# 8266_NFC_reader.net
KiCad netlist of a schematic drawn in EasyEDA
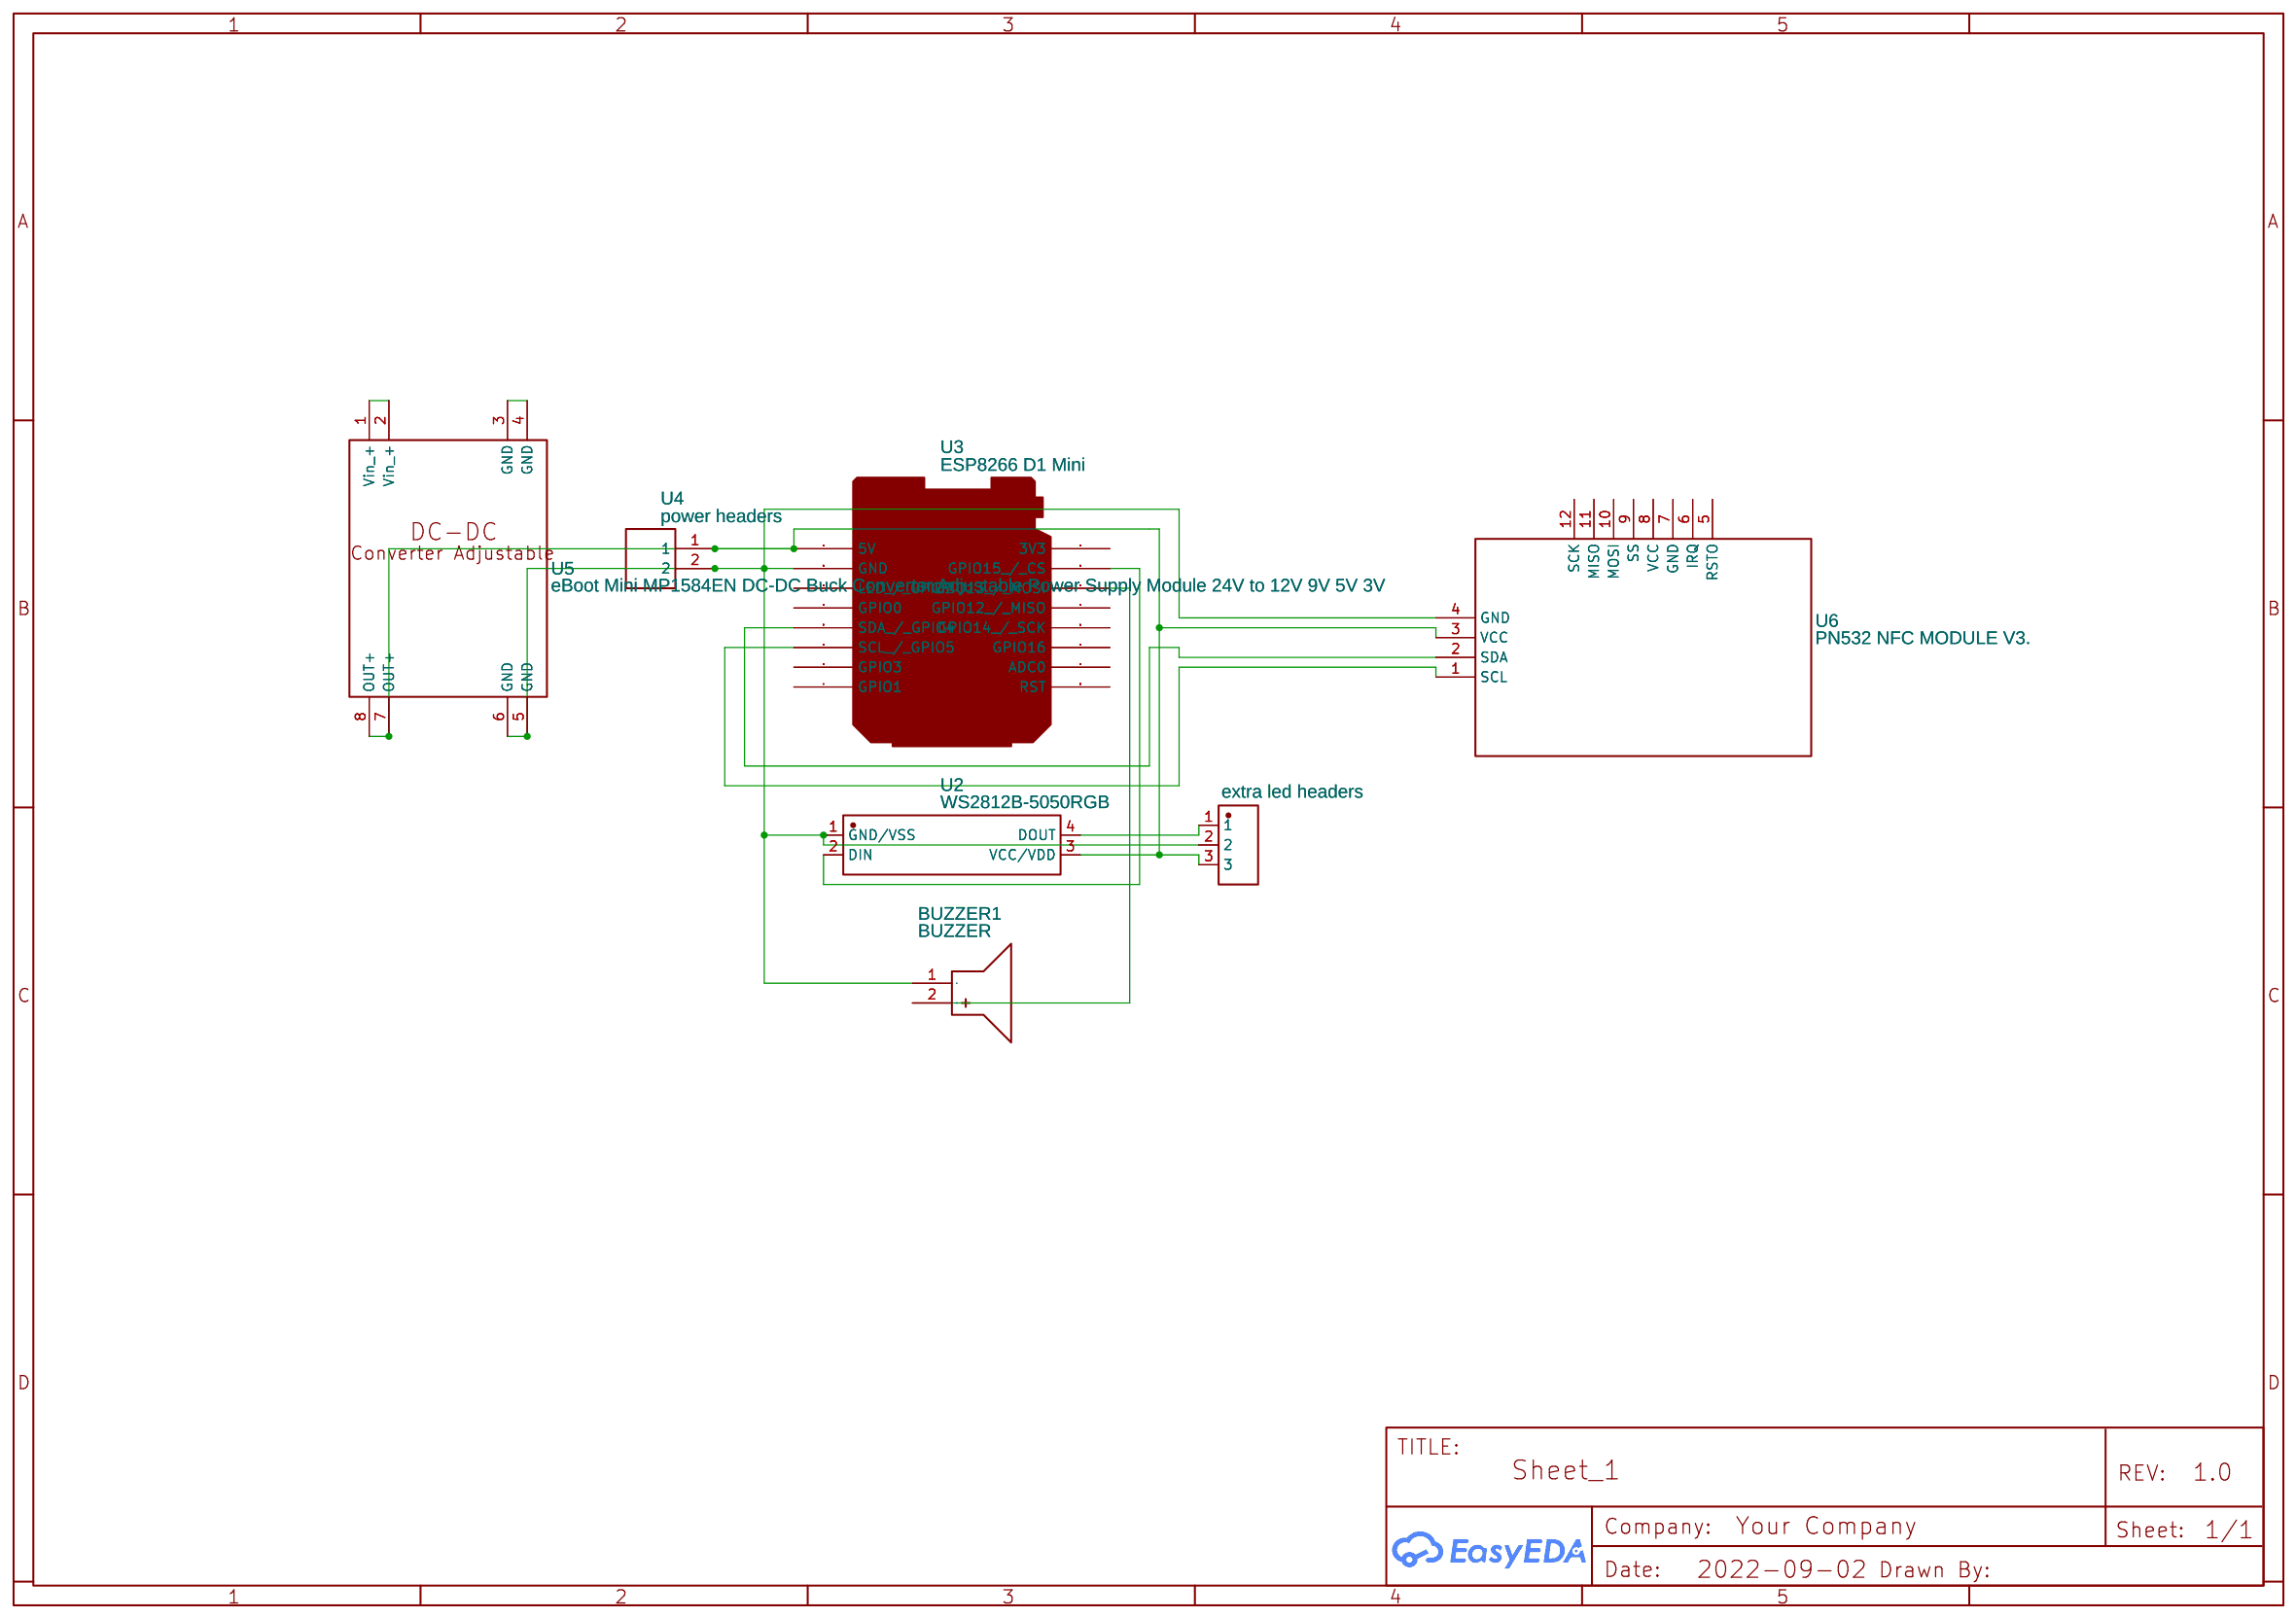
[diagram p0: schematic sheet]

(export (version "E")
  (design (tool "Eeschema 10.0.6"))
  (components
    (comp (ref "1")
      (value "extra led headers")
      (libsource (lib "") (part "Pin Headers 1x03 P P=2.54mm Droit M"))
    )
    (comp (ref "BUZZER1")
      (value "BUZZER")
      (fields
        (field (name "BOM_Manufacturer Part") "buzzer")
        (field (name "BOM_Supplier Part") "C9900014030")
      )
      (libsource (lib "") (part "BUZZER"))
    )
    (comp (ref "U2")
      (value "WS2812B-5050RGB")
      (fields (field (name "BOM_Supplier Part") "C2838584"))
      (libsource (lib "") (part "WS2812B-5050RGB"))
    )
    (comp (ref "U3") (value "ESP8266 D1 Mini") (libsource (lib "") (part "ESP8266 D1 Mini")))
    (comp (ref "U4")
      (value "power headers")
      (fields (field (name "BOM_Supplier Part") "7106"))
      (libsource (lib "") (part "1X2 HEADERS 2.54MM PITCH"))
    )
    (comp (ref "U5")
      (value "eBoot Mini MP1584EN DC-DC Buck Converter Adjustable Power Supply Module 24V to 12V 9V 5V 3V")
      (libsource (lib "") (part "eBoot Mini MP1584EN DC-DC Buck Converter Adjustable Power Supply Module 24V to 12V 9V 5V 3V"))
    )
    (comp (ref "U6") (value "PN532 NFC MODULE V3.") (libsource (lib "") (part "PN532 NFC MODULE V3.")))
  )
  (nets
    (net (code "1") (name "Net-(BUZZER1-+)") (class "Default")
      (node (ref "BUZZER1") (pin "2") (pinfunction "+_2") (pintype "unspecified"))
      (node (ref "U3") (pin "D7") (pinfunction "GPIO13_/_MOSI_D7") (pintype "bidirectional"))
    )
    (net (code "2") (name "Net-(BUZZER1--)") (class "Default")
      (node (ref "1") (pin "2") (pinfunction "2_2") (pintype "unspecified"))
      (node (ref "BUZZER1") (pin "1") (pinfunction "-_1") (pintype "unspecified"))
      (node (ref "U2") (pin "1") (pinfunction "GND/VSS_1") (pintype "unspecified"))
      (node (ref "U3") (pin "GND") (pinfunction "GND_GND") (pintype "passive"))
      (node (ref "U4") (pin "2") (pinfunction "2_2") (pintype "unspecified"))
      (node (ref "U5") (pin "5") (pinfunction "GND_5") (pintype "unspecified"))
      (node (ref "U5") (pin "6") (pinfunction "GND_6") (pintype "unspecified"))
      (node (ref "U6") (pin "4") (pinfunction "GND_4") (pintype "unspecified"))
    )
    (net (code "3") (name "Net-(U2-DIN)") (class "Default")
      (node (ref "U2") (pin "2") (pinfunction "DIN_2") (pintype "unspecified"))
      (node (ref "U3") (pin "D8") (pinfunction "GPIO15_/_CS_D8") (pintype "bidirectional"))
    )
    (net (code "4") (name "Net-(U2-DOUT)") (class "Default")
      (node (ref "1") (pin "1") (pinfunction "1_1") (pintype "unspecified"))
      (node (ref "U2") (pin "4") (pinfunction "DOUT_4") (pintype "unspecified"))
    )
    (net (code "5") (name "Net-(U2-VCC{slash}VDD)") (class "Default")
      (node (ref "1") (pin "3") (pinfunction "3_3") (pintype "unspecified"))
      (node (ref "U2") (pin "3") (pinfunction "VCC/VDD_3") (pintype "unspecified"))
      (node (ref "U3") (pin "5V") (pinfunction "5V_5V") (pintype "passive"))
      (node (ref "U4") (pin "1") (pinfunction "1_1") (pintype "unspecified"))
      (node (ref "U5") (pin "7") (pinfunction "OUT+_7") (pintype "unspecified"))
      (node (ref "U5") (pin "8") (pinfunction "OUT+_8") (pintype "unspecified"))
      (node (ref "U6") (pin "3") (pinfunction "VCC_3") (pintype "unspecified"))
    )
    (net (code "6") (name "Net-(U3-SCL_{slash}_GPIO5)") (class "Default")
      (node (ref "U3") (pin "D1") (pinfunction "SCL_/_GPIO5_D1") (pintype "bidirectional"))
      (node (ref "U6") (pin "1") (pinfunction "SCL_1") (pintype "unspecified"))
    )
    (net (code "7") (name "Net-(U3-SDA_{slash}_GPIO4)") (class "Default")
      (node (ref "U3") (pin "D2") (pinfunction "SDA_/_GPIO4_D2") (pintype "bidirectional"))
      (node (ref "U6") (pin "2") (pinfunction "SDA_2") (pintype "unspecified"))
    )
    (net (code "8") (name "Net-(U5-GND-Pad3)") (class "Default")
      (node (ref "U5") (pin "3") (pinfunction "GND_3") (pintype "unspecified"))
      (node (ref "U5") (pin "4") (pinfunction "GND_4") (pintype "unspecified"))
    )
    (net (code "9") (name "Net-(U5-Vin_+-Pad1)") (class "Default")
      (node (ref "U5") (pin "1") (pinfunction "Vin_+_1") (pintype "unspecified"))
      (node (ref "U5") (pin "2") (pinfunction "Vin_+_2") (pintype "unspecified"))
    )
    (net (code "10") (name "unconnected-(U3-ADC0-PadA0)") (class "Default")
      (node (ref "U3") (pin "A0") (pinfunction "ADC0_A0") (pintype "input"))
    )
    (net (code "11") (name "unconnected-(U3-GPIO0-PadD3)") (class "Default")
      (node (ref "U3") (pin "D3") (pinfunction "GPIO0_D3") (pintype "bidirectional"))
    )
    (net (code "12") (name "unconnected-(U3-GPIO1-PadTX)") (class "Default")
      (node (ref "U3") (pin "TX") (pinfunction "GPIO1_TX") (pintype "bidirectional"))
    )
    (net (code "13") (name "unconnected-(U3-GPIO3-PadRX)") (class "Default")
      (node (ref "U3") (pin "RX") (pinfunction "GPIO3_RX") (pintype "bidirectional"))
    )
    (net (code "14") (name "unconnected-(U3-GPIO12_{slash}_MISO-PadD6)") (class "Default")
      (node (ref "U3") (pin "D6") (pinfunction "GPIO12_/_MISO_D6") (pintype "bidirectional"))
    )
    (net (code "15") (name "unconnected-(U3-GPIO14_{slash}_SCK-PadD5)") (class "Default")
      (node (ref "U3") (pin "D5") (pinfunction "GPIO14_/_SCK_D5") (pintype "bidirectional"))
    )
    (net (code "16") (name "unconnected-(U3-GPIO16-PadD0)") (class "Default")
      (node (ref "U3") (pin "D0") (pinfunction "GPIO16_D0") (pintype "bidirectional"))
    )
    (net (code "17") (name "unconnected-(U3-LED_{slash}_GPIO2-PadD4)") (class "Default")
      (node (ref "U3") (pin "D4") (pinfunction "LED_/_GPIO2_D4") (pintype "bidirectional"))
    )
    (net (code "18") (name "unconnected-(U3-Pad3V3)") (class "Default")
      (node (ref "U3") (pin "3V3") (pinfunction "3V3_3V3") (pintype "passive"))
    )
    (net (code "19") (name "unconnected-(U3-PadRST)") (class "Default")
      (node (ref "U3") (pin "RST") (pinfunction "RST_RST") (pintype "input"))
    )
    (net (code "20") (name "unconnected-(U6-GND-Pad7)") (class "Default")
      (node (ref "U6") (pin "7") (pinfunction "GND_7") (pintype "unspecified"))
    )
    (net (code "21") (name "unconnected-(U6-IRQ-Pad6)") (class "Default")
      (node (ref "U6") (pin "6") (pinfunction "IRQ_6") (pintype "unspecified"))
    )
    (net (code "22") (name "unconnected-(U6-MISO-Pad11)") (class "Default")
      (node (ref "U6") (pin "11") (pinfunction "MISO_11") (pintype "unspecified"))
    )
    (net (code "23") (name "unconnected-(U6-MOSI-Pad10)") (class "Default")
      (node (ref "U6") (pin "10") (pinfunction "MOSI_10") (pintype "unspecified"))
    )
    (net (code "24") (name "unconnected-(U6-RSTO-Pad5)") (class "Default")
      (node (ref "U6") (pin "5") (pinfunction "RSTO_5") (pintype "unspecified"))
    )
    (net (code "25") (name "unconnected-(U6-SCK-Pad12)") (class "Default")
      (node (ref "U6") (pin "12") (pinfunction "SCK_12") (pintype "unspecified"))
    )
    (net (code "26") (name "unconnected-(U6-SS-Pad9)") (class "Default")
      (node (ref "U6") (pin "9") (pinfunction "SS_9") (pintype "unspecified"))
    )
    (net (code "27") (name "unconnected-(U6-VCC-Pad8)") (class "Default")
      (node (ref "U6") (pin "8") (pinfunction "VCC_8") (pintype "unspecified"))
    )
  )
)
